# Micro.net
KiCad netlist of a schematic drawn in Altium Designer
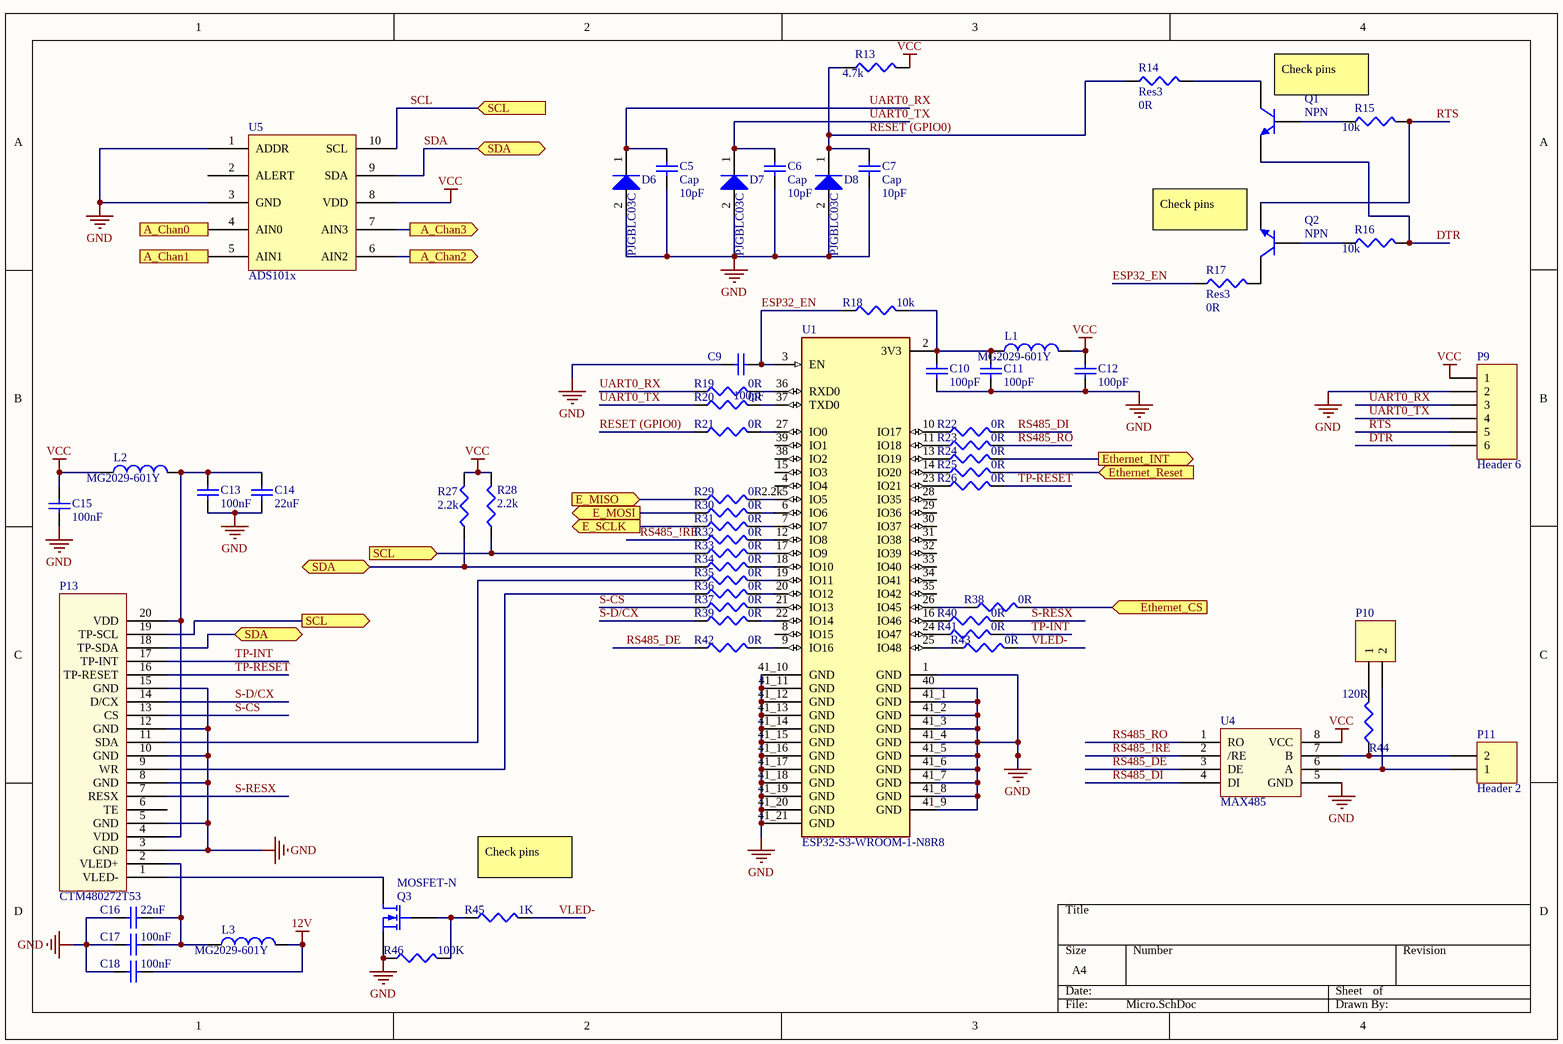
[diagram p0: Micro.SchDoc]

(export (version "E")
  (design (tool "Eeschema 10.0.6"))
  (components
    (comp (ref "C5")
      (value "Cap")
      (footprint "CAPC2012X04M")
      (description "Capacitor")
      (fields (field (name "ALTIUM_VALUE") "10pF") (field (name "PUBLISHER") "Altium Limited"))
      (libsource (lib "Miscellaneous Devices") (part "Cap"))
    )
    (comp (ref "C6")
      (value "Cap")
      (footprint "CAPC2012X04M")
      (description "Capacitor")
      (fields (field (name "ALTIUM_VALUE") "10pF") (field (name "PUBLISHER") "Altium Limited"))
      (libsource (lib "Miscellaneous Devices") (part "Cap"))
    )
    (comp (ref "C7")
      (value "Cap")
      (footprint "CAPC2012X04M")
      (description "Capacitor")
      (fields (field (name "ALTIUM_VALUE") "10pF") (field (name "PUBLISHER") "Altium Limited"))
      (libsource (lib "Miscellaneous Devices") (part "Cap"))
    )
    (comp (ref "C9")
      (value "100pF")
      (footprint "CAPC2012X04M")
      (description "Capacitor")
      (fields (field (name "Comment") "Cap") (field (name "PUBLISHER") "Altium Limited"))
      (libsource (lib "Miscellaneous Devices") (part "Cap"))
    )
    (comp (ref "C10")
      (value "100pF")
      (footprint "CAPC2012X04M")
      (description "Capacitor")
      (fields (field (name "Comment") "Cap") (field (name "PUBLISHER") "Altium Limited"))
      (libsource (lib "Miscellaneous Devices") (part "Cap"))
    )
    (comp (ref "C11")
      (value "100pF")
      (footprint "CAPC2012X04M")
      (description "Capacitor")
      (fields (field (name "Comment") "Cap") (field (name "PUBLISHER") "Altium Limited"))
      (libsource (lib "Miscellaneous Devices") (part "Cap"))
    )
    (comp (ref "C12")
      (value "100pF")
      (footprint "CAPC2012X04M")
      (description "Capacitor")
      (fields (field (name "Comment") "Cap") (field (name "PUBLISHER") "Altium Limited"))
      (libsource (lib "Miscellaneous Devices") (part "Cap"))
    )
    (comp (ref "C13")
      (value "100nF")
      (footprint "CAPC2012X04M")
      (description "Capacitor")
      (fields (field (name "Comment") "Cap") (field (name "PUBLISHER") "Altium Limited"))
      (libsource (lib "Miscellaneous Devices") (part "Cap"))
    )
    (comp (ref "C14")
      (value "22uF")
      (footprint "CAPC2012X04M")
      (description "Capacitor")
      (fields (field (name "Comment") "Cap") (field (name "PUBLISHER") "Altium Limited"))
      (libsource (lib "Miscellaneous Devices") (part "Cap"))
    )
    (comp (ref "C15")
      (value "100nF")
      (footprint "CAPC2012X04M")
      (description "Capacitor")
      (fields (field (name "Comment") "Cap") (field (name "PUBLISHER") "Altium Limited"))
      (libsource (lib "Miscellaneous Devices") (part "Cap"))
    )
    (comp (ref "C16")
      (value "22uF")
      (footprint "CAPC2012X04M")
      (description "Capacitor")
      (fields (field (name "Comment") "Cap") (field (name "PUBLISHER") "Altium Limited"))
      (libsource (lib "Miscellaneous Devices") (part "Cap"))
    )
    (comp (ref "C17")
      (value "100nF")
      (footprint "CAPC2012X04M")
      (description "Capacitor")
      (fields (field (name "Comment") "Cap") (field (name "PUBLISHER") "Altium Limited"))
      (libsource (lib "Miscellaneous Devices") (part "Cap"))
    )
    (comp (ref "C18")
      (value "100nF")
      (footprint "CAPC2012X04M")
      (description "Capacitor")
      (fields (field (name "Comment") "Cap") (field (name "PUBLISHER") "Altium Limited"))
      (libsource (lib "Miscellaneous Devices") (part "Cap"))
    )
    (comp (ref "D6")
      (value "PJGBLC03C")
      (footprint "DIOC2012X04M")
      (fields (field (name "PARTNUMBER") "SP4021-01FTG") (field (name "MANUFACTURER") "Littelfuse"))
      (libsource (lib "Diodes-TVS") (part "SP4021-01FTG"))
    )
    (comp (ref "D7")
      (value "PJGBLC03C")
      (footprint "DIOC2012X04M")
      (fields (field (name "PARTNUMBER") "SP4021-01FTG") (field (name "MANUFACTURER") "Littelfuse"))
      (libsource (lib "Diodes-TVS") (part "SP4021-01FTG"))
    )
    (comp (ref "D8")
      (value "PJGBLC03C")
      (footprint "DIOC2012X04M")
      (fields (field (name "PARTNUMBER") "SP4021-01FTG") (field (name "MANUFACTURER") "Littelfuse"))
      (libsource (lib "Diodes-TVS") (part "SP4021-01FTG"))
    )
    (comp (ref "L1")
      (value "MG2029-601Y")
      (footprint "RESC2012X04M")
      (description "Inductor")
      (fields (field (name "PUBLISHER") "Altium Limited"))
      (libsource (lib "Miscellaneous Devices") (part "Inductor"))
    )
    (comp (ref "L2")
      (value "MG2029-601Y")
      (footprint "RESC2012X04M")
      (description "Inductor")
      (fields (field (name "PUBLISHER") "Altium Limited"))
      (libsource (lib "Miscellaneous Devices") (part "Inductor"))
    )
    (comp (ref "L3")
      (value "MG2029-601Y")
      (footprint "RESC2012X04M")
      (description "Inductor")
      (fields (field (name "PUBLISHER") "Altium Limited"))
      (libsource (lib "Miscellaneous Devices") (part "Inductor"))
    )
    (comp (ref "P9")
      (value "Header 6")
      (footprint "HDR1X6")
      (description "Header, 6-Pin")
      (fields (field (name "PUBLISHER") "Altium Limited"))
      (libsource (lib "Miscellaneous Connectors") (part "Header 6"))
    )
    (comp (ref "P10")
      (value "Header 2")
      (footprint "HDR1X2")
      (description "Header, 2-Pin")
      (fields (field (name "PUBLISHER") "Altium Limited"))
      (libsource (lib "Miscellaneous Connectors") (part "Header 2"))
    )
    (comp (ref "P11")
      (value "Header 2")
      (footprint "WURTH- WR-TBL 2pin 5mmpitch")
      (description "Header, 2-Pin")
      (fields (field (name "PUBLISHER") "Altium Limited"))
      (libsource (lib "Miscellaneous Connectors") (part "Header 2"))
    )
    (comp (ref "P13")
      (value "CTM480272T53")
      (footprint "CF31201D0R0-05-NH")
      (libsource (lib "Parts") (part "CTM480272T53"))
    )
    (comp (ref "Q1")
      (value "NPN")
      (footprint "SOT95P245X110-3N")
      (description "NPN Bipolar Transistor")
      (fields (field (name "PUBLISHER") "Altium Limited"))
      (libsource (lib "Miscellaneous Devices") (part "NPN"))
    )
    (comp (ref "Q2")
      (value "NPN")
      (footprint "SOT95P245X110-3N")
      (description "NPN Bipolar Transistor")
      (fields (field (name "PUBLISHER") "Altium Limited"))
      (libsource (lib "Miscellaneous Devices") (part "NPN"))
    )
    (comp (ref "Q3")
      (value "MOSFET-N")
      (footprint "SOT95P245X110-3N")
      (description "N-Channel MOSFET")
      (fields (field (name "PUBLISHER") "Altium Limited"))
      (libsource (lib "Miscellaneous Devices") (part "MOSFET-N"))
    )
    (comp (ref "R13")
      (value "4.7k")
      (footprint "RESC2012X04M")
      (description "Resistor")
      (fields (field (name "Comment") "Res3") (field (name "PUBLISHER") "Altium Limited"))
      (libsource (lib "Miscellaneous Devices") (part "Res3"))
    )
    (comp (ref "R14")
      (value "Res3")
      (footprint "RESC2012X04M")
      (description "Resistor")
      (fields (field (name "ALTIUM_VALUE") "0R") (field (name "PUBLISHER") "Altium Limited"))
      (libsource (lib "Miscellaneous Devices") (part "Res3"))
    )
    (comp (ref "R15")
      (value "10k")
      (footprint "RESC2012X04M")
      (description "Resistor")
      (fields (field (name "Comment") "Res3") (field (name "PUBLISHER") "Altium Limited"))
      (libsource (lib "Miscellaneous Devices") (part "Res3"))
    )
    (comp (ref "R16")
      (value "10k")
      (footprint "RESC2012X04M")
      (description "Resistor")
      (fields (field (name "Comment") "Res3") (field (name "PUBLISHER") "Altium Limited"))
      (libsource (lib "Miscellaneous Devices") (part "Res3"))
    )
    (comp (ref "R17")
      (value "Res3")
      (footprint "RESC2012X04M")
      (description "Resistor")
      (fields (field (name "ALTIUM_VALUE") "0R") (field (name "PUBLISHER") "Altium Limited"))
      (libsource (lib "Miscellaneous Devices") (part "Res3"))
    )
    (comp (ref "R18")
      (value "10k")
      (footprint "RESC2012X04M")
      (description "Resistor")
      (fields (field (name "Comment") "Res3") (field (name "PUBLISHER") "Altium Limited"))
      (libsource (lib "Miscellaneous Devices") (part "Res3"))
    )
    (comp (ref "R19")
      (value "0R")
      (footprint "RESC2012X04M")
      (description "Resistor")
      (fields (field (name "Comment") "Res3") (field (name "PUBLISHER") "Altium Limited"))
      (libsource (lib "Miscellaneous Devices") (part "Res3"))
    )
    (comp (ref "R20")
      (value "0R")
      (footprint "RESC2012X04M")
      (description "Resistor")
      (fields (field (name "Comment") "Res3") (field (name "PUBLISHER") "Altium Limited"))
      (libsource (lib "Miscellaneous Devices") (part "Res3"))
    )
    (comp (ref "R21")
      (value "0R")
      (footprint "RESC2012X04M")
      (description "Resistor")
      (fields (field (name "Comment") "Res3") (field (name "PUBLISHER") "Altium Limited"))
      (libsource (lib "Miscellaneous Devices") (part "Res3"))
    )
    (comp (ref "R22")
      (value "0R")
      (footprint "RESC2012X04M")
      (description "Resistor")
      (fields (field (name "Comment") "Res3") (field (name "PUBLISHER") "Altium Limited"))
      (libsource (lib "Miscellaneous Devices") (part "Res3"))
    )
    (comp (ref "R23")
      (value "0R")
      (footprint "RESC2012X04M")
      (description "Resistor")
      (fields (field (name "Comment") "Res3") (field (name "PUBLISHER") "Altium Limited"))
      (libsource (lib "Miscellaneous Devices") (part "Res3"))
    )
    (comp (ref "R24")
      (value "0R")
      (footprint "RESC2012X04M")
      (description "Resistor")
      (fields (field (name "Comment") "Res3") (field (name "PUBLISHER") "Altium Limited"))
      (libsource (lib "Miscellaneous Devices") (part "Res3"))
    )
    (comp (ref "R25")
      (value "0R")
      (footprint "RESC2012X04M")
      (description "Resistor")
      (fields (field (name "Comment") "Res3") (field (name "PUBLISHER") "Altium Limited"))
      (libsource (lib "Miscellaneous Devices") (part "Res3"))
    )
    (comp (ref "R26")
      (value "0R")
      (footprint "RESC2012X04M")
      (description "Resistor")
      (fields (field (name "Comment") "Res3") (field (name "PUBLISHER") "Altium Limited"))
      (libsource (lib "Miscellaneous Devices") (part "Res3"))
    )
    (comp (ref "R27")
      (value "2.2k")
      (footprint "RESC2012X04M")
      (description "Resistor")
      (fields (field (name "Comment") "Res3") (field (name "PUBLISHER") "Altium Limited"))
      (libsource (lib "Miscellaneous Devices") (part "Res3"))
    )
    (comp (ref "R28")
      (value "2.2k")
      (footprint "RESC2012X04M")
      (description "Resistor")
      (fields (field (name "Comment") "Res3") (field (name "PUBLISHER") "Altium Limited"))
      (libsource (lib "Miscellaneous Devices") (part "Res3"))
    )
    (comp (ref "R29")
      (value "0R")
      (footprint "RESC2012X04M")
      (description "Resistor")
      (fields (field (name "Comment") "Res3") (field (name "PUBLISHER") "Altium Limited"))
      (libsource (lib "Miscellaneous Devices") (part "Res3"))
    )
    (comp (ref "R30")
      (value "0R")
      (footprint "RESC2012X04M")
      (description "Resistor")
      (fields (field (name "Comment") "Res3") (field (name "PUBLISHER") "Altium Limited"))
      (libsource (lib "Miscellaneous Devices") (part "Res3"))
    )
    (comp (ref "R31")
      (value "0R")
      (footprint "RESC2012X04M")
      (description "Resistor")
      (fields (field (name "Comment") "Res3") (field (name "PUBLISHER") "Altium Limited"))
      (libsource (lib "Miscellaneous Devices") (part "Res3"))
    )
    (comp (ref "R32")
      (value "0R")
      (footprint "RESC2012X04M")
      (description "Resistor")
      (fields (field (name "Comment") "Res3") (field (name "PUBLISHER") "Altium Limited"))
      (libsource (lib "Miscellaneous Devices") (part "Res3"))
    )
    (comp (ref "R33")
      (value "0R")
      (footprint "RESC2012X04M")
      (description "Resistor")
      (fields (field (name "Comment") "Res3") (field (name "PUBLISHER") "Altium Limited"))
      (libsource (lib "Miscellaneous Devices") (part "Res3"))
    )
    (comp (ref "R34")
      (value "0R")
      (footprint "RESC2012X04M")
      (description "Resistor")
      (fields (field (name "Comment") "Res3") (field (name "PUBLISHER") "Altium Limited"))
      (libsource (lib "Miscellaneous Devices") (part "Res3"))
    )
    (comp (ref "R35")
      (value "0R")
      (footprint "RESC2012X04M")
      (description "Resistor")
      (fields (field (name "Comment") "Res3") (field (name "PUBLISHER") "Altium Limited"))
      (libsource (lib "Miscellaneous Devices") (part "Res3"))
    )
    (comp (ref "R36")
      (value "0R")
      (footprint "RESC2012X04M")
      (description "Resistor")
      (fields (field (name "Comment") "Res3") (field (name "PUBLISHER") "Altium Limited"))
      (libsource (lib "Miscellaneous Devices") (part "Res3"))
    )
    (comp (ref "R37")
      (value "0R")
      (footprint "RESC2012X04M")
      (description "Resistor")
      (fields (field (name "Comment") "Res3") (field (name "PUBLISHER") "Altium Limited"))
      (libsource (lib "Miscellaneous Devices") (part "Res3"))
    )
    (comp (ref "R38")
      (value "0R")
      (footprint "RESC2012X04M")
      (description "Resistor")
      (fields (field (name "Comment") "Res3") (field (name "PUBLISHER") "Altium Limited"))
      (libsource (lib "Miscellaneous Devices") (part "Res3"))
    )
    (comp (ref "R39")
      (value "0R")
      (footprint "RESC2012X04M")
      (description "Resistor")
      (fields (field (name "Comment") "Res3") (field (name "PUBLISHER") "Altium Limited"))
      (libsource (lib "Miscellaneous Devices") (part "Res3"))
    )
    (comp (ref "R40")
      (value "0R")
      (footprint "RESC2012X04M")
      (description "Resistor")
      (fields (field (name "Comment") "Res3") (field (name "PUBLISHER") "Altium Limited"))
      (libsource (lib "Miscellaneous Devices") (part "Res3"))
    )
    (comp (ref "R41")
      (value "0R")
      (footprint "RESC2012X04M")
      (description "Resistor")
      (fields (field (name "Comment") "Res3") (field (name "PUBLISHER") "Altium Limited"))
      (libsource (lib "Miscellaneous Devices") (part "Res3"))
    )
    (comp (ref "R42")
      (value "0R")
      (footprint "RESC2012X04M")
      (description "Resistor")
      (fields (field (name "Comment") "Res3") (field (name "PUBLISHER") "Altium Limited"))
      (libsource (lib "Miscellaneous Devices") (part "Res3"))
    )
    (comp (ref "R43")
      (value "0R")
      (footprint "RESC2012X04M")
      (description "Resistor")
      (fields (field (name "Comment") "Res3") (field (name "PUBLISHER") "Altium Limited"))
      (libsource (lib "Miscellaneous Devices") (part "Res3"))
    )
    (comp (ref "R44")
      (value "120R")
      (footprint "RESC2012X04M")
      (description "Resistor")
      (fields (field (name "Comment") "Res3") (field (name "PUBLISHER") "Altium Limited"))
      (libsource (lib "Miscellaneous Devices") (part "Res3"))
    )
    (comp (ref "R45")
      (value "1K")
      (footprint "RESC2012X04M")
      (description "Resistor")
      (fields (field (name "Comment") "Res3") (field (name "PUBLISHER") "Altium Limited"))
      (libsource (lib "Miscellaneous Devices") (part "Res3"))
    )
    (comp (ref "R46")
      (value "100K")
      (footprint "RESC2012X04M")
      (description "Resistor")
      (fields (field (name "Comment") "Res3") (field (name "PUBLISHER") "Altium Limited"))
      (libsource (lib "Miscellaneous Devices") (part "Res3"))
    )
    (comp (ref "U1")
      (value "ESP32-S3-WROOM-1-N8R8")
      (footprint "XCVR_ESP32S3WROOM1N8R8")
      (description "Bluetooth, WiFi 802.11b/g/n, Bluetooth v5.0 Transceiver Module 2.4GHz PCB Trace Surface Mount")
      (fields (field (name "MF") "Espressif Systems"))
      (libsource (lib "ESP32-S3-WROOM-1-N8R8") (part "ESP32-S3-WROOM-1-N8R8"))
    )
    (comp (ref "U4")
      (value "MAX485")
      (footprint "SOIC127P600X155-8N")
      (libsource (lib "Parts") (part "MAX485"))
    )
    (comp (ref "U5") (value "ADS101x") (footprint "VSSOP_10") (libsource (lib "Parts") (part "ADS101x")))
  )
  (nets
    (net (code "1") (name "/A_Chan0") (class "Default")
      (node (ref "U5") (pin "4") (pinfunction "AIN0_4") (pintype "passive"))
    )
    (net (code "2") (name "/A_Chan1") (class "Default")
      (node (ref "U5") (pin "5") (pinfunction "AIN1_5") (pintype "passive"))
    )
    (net (code "3") (name "/A_Chan2") (class "Default")
      (node (ref "U5") (pin "6") (pinfunction "AIN2_6") (pintype "passive"))
    )
    (net (code "4") (name "/A_Chan3") (class "Default")
      (node (ref "U5") (pin "7") (pinfunction "AIN3_7") (pintype "passive"))
    )
    (net (code "5") (name "/DTR") (class "Default")
      (node (ref "P9") (pin "6") (pinfunction "6_6") (pintype "passive"))
      (node (ref "Q1") (pin "3") (pinfunction "E_3") (pintype "passive"))
      (node (ref "R16") (pin "2") (pinfunction "2_2") (pintype "passive"))
    )
    (net (code "6") (name "/ESP32_EN") (class "Default")
      (node (ref "C9") (pin "1") (pinfunction "1_1") (pintype "passive"))
      (node (ref "R17") (pin "1") (pinfunction "1_1") (pintype "passive"))
      (node (ref "R18") (pin "1") (pinfunction "1_1") (pintype "passive"))
      (node (ref "U1") (pin "3") (pinfunction "EN_3") (pintype "input"))
    )
    (net (code "7") (name "/E_MISO") (class "Default")
      (node (ref "R29") (pin "1") (pinfunction "1_1") (pintype "passive"))
    )
    (net (code "8") (name "/E_MOSI") (class "Default")
      (node (ref "R30") (pin "1") (pinfunction "1_1") (pintype "passive"))
    )
    (net (code "9") (name "/E_SCLK") (class "Default")
      (node (ref "R31") (pin "1") (pinfunction "1_1") (pintype "passive"))
    )
    (net (code "10") (name "/Ethernet_CS") (class "Default")
      (node (ref "R38") (pin "2") (pinfunction "2_2") (pintype "passive"))
    )
    (net (code "11") (name "/Ethernet_INT") (class "Default")
      (node (ref "R24") (pin "2") (pinfunction "2_2") (pintype "passive"))
    )
    (net (code "12") (name "/Ethernet_Reset") (class "Default")
      (node (ref "R25") (pin "2") (pinfunction "2_2") (pintype "passive"))
    )
    (net (code "13") (name "/RESET (GPIO0)") (class "Default")
      (node (ref "C7") (pin "2") (pinfunction "2_2") (pintype "passive"))
      (node (ref "D8") (pin "1") (pinfunction "K_1") (pintype "passive"))
      (node (ref "R13") (pin "1") (pinfunction "1_1") (pintype "passive"))
      (node (ref "R14") (pin "1") (pinfunction "1_1") (pintype "passive"))
      (node (ref "R21") (pin "1") (pinfunction "1_1") (pintype "passive"))
    )
    (net (code "14") (name "/RS485_!RE") (class "Default")
      (node (ref "R32") (pin "1") (pinfunction "1_1") (pintype "passive"))
      (node (ref "U4") (pin "2") (pinfunction "/RE_2") (pintype "passive"))
    )
    (net (code "15") (name "/RS485_DE") (class "Default")
      (node (ref "R42") (pin "1") (pinfunction "1_1") (pintype "passive"))
      (node (ref "U4") (pin "3") (pinfunction "DE_3") (pintype "passive"))
    )
    (net (code "16") (name "/RS485_DI") (class "Default")
      (node (ref "R22") (pin "2") (pinfunction "2_2") (pintype "passive"))
      (node (ref "U4") (pin "4") (pinfunction "DI_4") (pintype "passive"))
    )
    (net (code "17") (name "/RS485_RO") (class "Default")
      (node (ref "R23") (pin "2") (pinfunction "2_2") (pintype "passive"))
      (node (ref "U4") (pin "1") (pinfunction "RO_1") (pintype "passive"))
    )
    (net (code "18") (name "/RTS") (class "Default")
      (node (ref "P9") (pin "5") (pinfunction "5_5") (pintype "passive"))
      (node (ref "Q2") (pin "3") (pinfunction "E_3") (pintype "passive"))
      (node (ref "R15") (pin "2") (pinfunction "2_2") (pintype "passive"))
    )
    (net (code "19") (name "/S-CS") (class "Default")
      (node (ref "P13") (pin "13") (pinfunction "CS_13") (pintype "passive"))
      (node (ref "R37") (pin "1") (pinfunction "1_1") (pintype "passive"))
    )
    (net (code "20") (name "/S-D{slash}CX") (class "Default")
      (node (ref "P13") (pin "14") (pinfunction "D/CX_14") (pintype "passive"))
      (node (ref "R39") (pin "1") (pinfunction "1_1") (pintype "passive"))
    )
    (net (code "21") (name "/S-RESX") (class "Default")
      (node (ref "P13") (pin "7") (pinfunction "RESX_7") (pintype "passive"))
      (node (ref "R40") (pin "2") (pinfunction "2_2") (pintype "passive"))
    )
    (net (code "22") (name "/SCL") (class "Default")
      (node (ref "P13") (pin "19") (pinfunction "TP-SCL_19") (pintype "passive"))
      (node (ref "R28") (pin "1") (pinfunction "1_1") (pintype "passive"))
      (node (ref "R33") (pin "1") (pinfunction "1_1") (pintype "passive"))
      (node (ref "U5") (pin "10") (pinfunction "SCL_10") (pintype "passive"))
    )
    (net (code "23") (name "/SDA") (class "Default")
      (node (ref "P13") (pin "18") (pinfunction "TP-SDA_18") (pintype "passive"))
      (node (ref "R27") (pin "1") (pinfunction "1_1") (pintype "passive"))
      (node (ref "R34") (pin "1") (pinfunction "1_1") (pintype "passive"))
      (node (ref "U5") (pin "9") (pinfunction "SDA_9") (pintype "passive"))
    )
    (net (code "24") (name "/TP-INT") (class "Default")
      (node (ref "P13") (pin "17") (pinfunction "TP-INT_17") (pintype "passive"))
      (node (ref "R41") (pin "2") (pinfunction "2_2") (pintype "passive"))
    )
    (net (code "25") (name "/TP-RESET") (class "Default")
      (node (ref "P13") (pin "16") (pinfunction "TP-RESET_16") (pintype "passive"))
      (node (ref "R26") (pin "2") (pinfunction "2_2") (pintype "passive"))
    )
    (net (code "26") (name "/UART0_RX") (class "Default")
      (node (ref "C5") (pin "2") (pinfunction "2_2") (pintype "passive"))
      (node (ref "D6") (pin "1") (pinfunction "K_1") (pintype "passive"))
      (node (ref "P9") (pin "3") (pinfunction "3_3") (pintype "passive"))
      (node (ref "R19") (pin "1") (pinfunction "1_1") (pintype "passive"))
    )
    (net (code "27") (name "/UART0_TX") (class "Default")
      (node (ref "C6") (pin "2") (pinfunction "2_2") (pintype "passive"))
      (node (ref "D7") (pin "1") (pinfunction "K_1") (pintype "passive"))
      (node (ref "P9") (pin "4") (pinfunction "4_4") (pintype "passive"))
      (node (ref "R20") (pin "1") (pinfunction "1_1") (pintype "passive"))
    )
    (net (code "28") (name "/VLED-") (class "Default")
      (node (ref "R43") (pin "2") (pinfunction "2_2") (pintype "passive"))
      (node (ref "R45") (pin "2") (pinfunction "2_2") (pintype "passive"))
    )
    (net (code "29") (name "12V") (class "Default")
      (node (ref "C18") (pin "1") (pinfunction "1_1") (pintype "passive"))
      (node (ref "L3") (pin "2") (pinfunction "2_2") (pintype "passive"))
    )
    (net (code "30") (name "GND") (class "Default")
      (node (ref "C10") (pin "2") (pinfunction "2_2") (pintype "passive"))
      (node (ref "C11") (pin "2") (pinfunction "2_2") (pintype "passive"))
      (node (ref "C12") (pin "2") (pinfunction "2_2") (pintype "passive"))
      (node (ref "C13") (pin "2") (pinfunction "2_2") (pintype "passive"))
      (node (ref "C14") (pin "2") (pinfunction "2_2") (pintype "passive"))
      (node (ref "C15") (pin "2") (pinfunction "2_2") (pintype "passive"))
      (node (ref "C16") (pin "2") (pinfunction "2_2") (pintype "passive"))
      (node (ref "C17") (pin "2") (pinfunction "2_2") (pintype "passive"))
      (node (ref "C18") (pin "2") (pinfunction "2_2") (pintype "passive"))
      (node (ref "C5") (pin "1") (pinfunction "1_1") (pintype "passive"))
      (node (ref "C6") (pin "1") (pinfunction "1_1") (pintype "passive"))
      (node (ref "C7") (pin "1") (pinfunction "1_1") (pintype "passive"))
      (node (ref "C9") (pin "2") (pinfunction "2_2") (pintype "passive"))
      (node (ref "D6") (pin "2") (pinfunction "A_2") (pintype "passive"))
      (node (ref "D7") (pin "2") (pinfunction "A_2") (pintype "passive"))
      (node (ref "D8") (pin "2") (pinfunction "A_2") (pintype "passive"))
      (node (ref "P13") (pin "10") (pinfunction "GND_10") (pintype "passive"))
      (node (ref "P13") (pin "12") (pinfunction "GND_12") (pintype "passive"))
      (node (ref "P13") (pin "15") (pinfunction "GND_15") (pintype "passive"))
      (node (ref "P13") (pin "3") (pinfunction "GND_3") (pintype "passive"))
      (node (ref "P13") (pin "5") (pinfunction "GND_5") (pintype "passive"))
      (node (ref "P13") (pin "8") (pinfunction "GND_8") (pintype "passive"))
      (node (ref "P9") (pin "2") (pinfunction "2_2") (pintype "passive"))
      (node (ref "Q3") (pin "3") (pinfunction "S_3") (pintype "passive"))
      (node (ref "R46") (pin "1") (pinfunction "1_1") (pintype "passive"))
      (node (ref "U1") (pin "1") (pinfunction "GND_1") (pintype "power_in"))
      (node (ref "U1") (pin "40") (pinfunction "GND_40") (pintype "power_in"))
      (node (ref "U1") (pin "41_1") (pinfunction "GND_41_1") (pintype "power_in"))
      (node (ref "U1") (pin "41_10") (pinfunction "GND_41_10") (pintype "passive"))
      (node (ref "U1") (pin "41_11") (pinfunction "GND_41_11") (pintype "passive"))
      (node (ref "U1") (pin "41_12") (pinfunction "GND_41_12") (pintype "passive"))
      (node (ref "U1") (pin "41_13") (pinfunction "GND_41_13") (pintype "passive"))
      (node (ref "U1") (pin "41_14") (pinfunction "GND_41_14") (pintype "passive"))
      (node (ref "U1") (pin "41_15") (pinfunction "GND_41_15") (pintype "passive"))
      (node (ref "U1") (pin "41_16") (pinfunction "GND_41_16") (pintype "passive"))
      (node (ref "U1") (pin "41_17") (pinfunction "GND_41_17") (pintype "passive"))
      (node (ref "U1") (pin "41_18") (pinfunction "GND_41_18") (pintype "passive"))
      (node (ref "U1") (pin "41_19") (pinfunction "GND_41_19") (pintype "passive"))
      (node (ref "U1") (pin "41_2") (pinfunction "GND_41_2") (pintype "power_in"))
      (node (ref "U1") (pin "41_20") (pinfunction "GND_41_20") (pintype "passive"))
      (node (ref "U1") (pin "41_21") (pinfunction "GND_41_21") (pintype "passive"))
      (node (ref "U1") (pin "41_3") (pinfunction "GND_41_3") (pintype "power_in"))
      (node (ref "U1") (pin "41_4") (pinfunction "GND_41_4") (pintype "power_in"))
      (node (ref "U1") (pin "41_5") (pinfunction "GND_41_5") (pintype "power_in"))
      (node (ref "U1") (pin "41_6") (pinfunction "GND_41_6") (pintype "power_in"))
      (node (ref "U1") (pin "41_7") (pinfunction "GND_41_7") (pintype "power_in"))
      (node (ref "U1") (pin "41_8") (pinfunction "GND_41_8") (pintype "power_in"))
      (node (ref "U1") (pin "41_9") (pinfunction "GND_41_9") (pintype "power_in"))
      (node (ref "U4") (pin "5") (pinfunction "GND_5") (pintype "passive"))
      (node (ref "U5") (pin "1") (pinfunction "ADDR_1") (pintype "passive"))
      (node (ref "U5") (pin "3") (pinfunction "GND_3") (pintype "passive"))
    )
    (net (code "31") (name "Net-(C13-Pad1)") (class "Default")
      (node (ref "C13") (pin "1") (pinfunction "1_1") (pintype "passive"))
      (node (ref "C14") (pin "1") (pinfunction "1_1") (pintype "passive"))
      (node (ref "L2") (pin "2") (pinfunction "2_2") (pintype "passive"))
      (node (ref "P13") (pin "20") (pinfunction "VDD_20") (pintype "passive"))
      (node (ref "P13") (pin "4") (pinfunction "VDD_4") (pintype "passive"))
    )
    (net (code "32") (name "Net-(P10-Pad1)") (class "Default")
      (node (ref "P10") (pin "1") (pinfunction "1_1") (pintype "passive"))
      (node (ref "R44") (pin "2") (pinfunction "2_2") (pintype "passive"))
    )
    (net (code "33") (name "Net-(P13-SDA)") (class "Default")
      (node (ref "P13") (pin "11") (pinfunction "SDA_11") (pintype "passive"))
      (node (ref "R35") (pin "1") (pinfunction "1_1") (pintype "passive"))
    )
    (net (code "34") (name "Net-(P13-VLED+)") (class "Default")
      (node (ref "C16") (pin "1") (pinfunction "1_1") (pintype "passive"))
      (node (ref "C17") (pin "1") (pinfunction "1_1") (pintype "passive"))
      (node (ref "L3") (pin "1") (pinfunction "1_1") (pintype "passive"))
      (node (ref "P13") (pin "2") (pinfunction "VLED+_2") (pintype "passive"))
    )
    (net (code "35") (name "Net-(P13-VLED-)") (class "Default")
      (node (ref "P13") (pin "1") (pinfunction "VLED-_1") (pintype "passive"))
      (node (ref "Q3") (pin "1") (pinfunction "D_1") (pintype "passive"))
    )
    (net (code "36") (name "Net-(P13-WR)") (class "Default")
      (node (ref "P13") (pin "9") (pinfunction "WR_9") (pintype "passive"))
      (node (ref "R36") (pin "1") (pinfunction "1_1") (pintype "passive"))
    )
    (net (code "37") (name "Net-(Q1-B)") (class "Default")
      (node (ref "Q1") (pin "2") (pinfunction "B_2") (pintype "passive"))
      (node (ref "R15") (pin "1") (pinfunction "1_1") (pintype "passive"))
    )
    (net (code "38") (name "Net-(Q1-C)") (class "Default")
      (node (ref "Q1") (pin "1") (pinfunction "C_1") (pintype "passive"))
      (node (ref "R14") (pin "2") (pinfunction "2_2") (pintype "passive"))
    )
    (net (code "39") (name "Net-(Q2-B)") (class "Default")
      (node (ref "Q2") (pin "2") (pinfunction "B_2") (pintype "passive"))
      (node (ref "R16") (pin "1") (pinfunction "1_1") (pintype "passive"))
    )
    (net (code "40") (name "Net-(Q2-C)") (class "Default")
      (node (ref "Q2") (pin "1") (pinfunction "C_1") (pintype "passive"))
      (node (ref "R17") (pin "2") (pinfunction "2_2") (pintype "passive"))
    )
    (net (code "41") (name "Net-(Q3-G)") (class "Default")
      (node (ref "Q3") (pin "2") (pinfunction "G_2") (pintype "passive"))
      (node (ref "R45") (pin "1") (pinfunction "1_1") (pintype "passive"))
      (node (ref "R46") (pin "2") (pinfunction "2_2") (pintype "passive"))
    )
    (net (code "42") (name "Net-(U1-3V3)") (class "Default")
      (node (ref "C10") (pin "1") (pinfunction "1_1") (pintype "passive"))
      (node (ref "C11") (pin "1") (pinfunction "1_1") (pintype "passive"))
      (node (ref "L1") (pin "1") (pinfunction "1_1") (pintype "passive"))
      (node (ref "R18") (pin "2") (pinfunction "2_2") (pintype "passive"))
      (node (ref "U1") (pin "2") (pinfunction "3V3_2") (pintype "power_in"))
    )
    (net (code "43") (name "Net-(U1-IO0)") (class "Default")
      (node (ref "R21") (pin "2") (pinfunction "2_2") (pintype "passive"))
      (node (ref "U1") (pin "27") (pinfunction "IO0_27") (pintype "bidirectional"))
    )
    (net (code "44") (name "Net-(U1-IO5)") (class "Default")
      (node (ref "R29") (pin "2") (pinfunction "2_2") (pintype "passive"))
      (node (ref "U1") (pin "5") (pinfunction "IO5_5") (pintype "bidirectional"))
    )
    (net (code "45") (name "Net-(U1-IO6)") (class "Default")
      (node (ref "R30") (pin "2") (pinfunction "2_2") (pintype "passive"))
      (node (ref "U1") (pin "6") (pinfunction "IO6_6") (pintype "bidirectional"))
    )
    (net (code "46") (name "Net-(U1-IO7)") (class "Default")
      (node (ref "R31") (pin "2") (pinfunction "2_2") (pintype "passive"))
      (node (ref "U1") (pin "7") (pinfunction "IO7_7") (pintype "bidirectional"))
    )
    (net (code "47") (name "Net-(U1-IO8)") (class "Default")
      (node (ref "R32") (pin "2") (pinfunction "2_2") (pintype "passive"))
      (node (ref "U1") (pin "12") (pinfunction "IO8_12") (pintype "bidirectional"))
    )
    (net (code "48") (name "Net-(U1-IO9)") (class "Default")
      (node (ref "R33") (pin "2") (pinfunction "2_2") (pintype "passive"))
      (node (ref "U1") (pin "17") (pinfunction "IO9_17") (pintype "bidirectional"))
    )
    (net (code "49") (name "Net-(U1-IO10)") (class "Default")
      (node (ref "R34") (pin "2") (pinfunction "2_2") (pintype "passive"))
      (node (ref "U1") (pin "18") (pinfunction "IO10_18") (pintype "bidirectional"))
    )
    (net (code "50") (name "Net-(U1-IO11)") (class "Default")
      (node (ref "R35") (pin "2") (pinfunction "2_2") (pintype "passive"))
      (node (ref "U1") (pin "19") (pinfunction "IO11_19") (pintype "bidirectional"))
    )
    (net (code "51") (name "Net-(U1-IO12)") (class "Default")
      (node (ref "R36") (pin "2") (pinfunction "2_2") (pintype "passive"))
      (node (ref "U1") (pin "20") (pinfunction "IO12_20") (pintype "bidirectional"))
    )
    (net (code "52") (name "Net-(U1-IO13)") (class "Default")
      (node (ref "R37") (pin "2") (pinfunction "2_2") (pintype "passive"))
      (node (ref "U1") (pin "21") (pinfunction "IO13_21") (pintype "bidirectional"))
    )
    (net (code "53") (name "Net-(U1-IO14)") (class "Default")
      (node (ref "R39") (pin "2") (pinfunction "2_2") (pintype "passive"))
      (node (ref "U1") (pin "22") (pinfunction "IO14_22") (pintype "bidirectional"))
    )
    (net (code "54") (name "Net-(U1-IO16)") (class "Default")
      (node (ref "R42") (pin "2") (pinfunction "2_2") (pintype "passive"))
      (node (ref "U1") (pin "9") (pinfunction "IO16_9") (pintype "bidirectional"))
    )
    (net (code "55") (name "Net-(U1-IO17)") (class "Default")
      (node (ref "R22") (pin "1") (pinfunction "1_1") (pintype "passive"))
      (node (ref "U1") (pin "10") (pinfunction "IO17_10") (pintype "bidirectional"))
    )
    (net (code "56") (name "Net-(U1-IO18)") (class "Default")
      (node (ref "R23") (pin "1") (pinfunction "1_1") (pintype "passive"))
      (node (ref "U1") (pin "11") (pinfunction "IO18_11") (pintype "bidirectional"))
    )
    (net (code "57") (name "Net-(U1-IO19)") (class "Default")
      (node (ref "R24") (pin "1") (pinfunction "1_1") (pintype "passive"))
      (node (ref "U1") (pin "13") (pinfunction "IO19_13") (pintype "bidirectional"))
    )
    (net (code "58") (name "Net-(U1-IO20)") (class "Default")
      (node (ref "R25") (pin "1") (pinfunction "1_1") (pintype "passive"))
      (node (ref "U1") (pin "14") (pinfunction "IO20_14") (pintype "bidirectional"))
    )
    (net (code "59") (name "Net-(U1-IO21)") (class "Default")
      (node (ref "R26") (pin "1") (pinfunction "1_1") (pintype "passive"))
      (node (ref "U1") (pin "23") (pinfunction "IO21_23") (pintype "bidirectional"))
    )
    (net (code "60") (name "Net-(U1-IO45)") (class "Default")
      (node (ref "R38") (pin "1") (pinfunction "1_1") (pintype "passive"))
      (node (ref "U1") (pin "26") (pinfunction "IO45_26") (pintype "bidirectional"))
    )
    (net (code "61") (name "Net-(U1-IO46)") (class "Default")
      (node (ref "R40") (pin "1") (pinfunction "1_1") (pintype "passive"))
      (node (ref "U1") (pin "16") (pinfunction "IO46_16") (pintype "bidirectional"))
    )
    (net (code "62") (name "Net-(U1-IO47)") (class "Default")
      (node (ref "R41") (pin "1") (pinfunction "1_1") (pintype "passive"))
      (node (ref "U1") (pin "24") (pinfunction "IO47_24") (pintype "bidirectional"))
    )
    (net (code "63") (name "Net-(U1-IO48)") (class "Default")
      (node (ref "R43") (pin "1") (pinfunction "1_1") (pintype "passive"))
      (node (ref "U1") (pin "25") (pinfunction "IO48_25") (pintype "bidirectional"))
    )
    (net (code "64") (name "Net-(U1-RXD0)") (class "Default")
      (node (ref "R19") (pin "2") (pinfunction "2_2") (pintype "passive"))
      (node (ref "U1") (pin "36") (pinfunction "RXD0_36") (pintype "bidirectional"))
    )
    (net (code "65") (name "Net-(U1-TXD0)") (class "Default")
      (node (ref "R20") (pin "2") (pinfunction "2_2") (pintype "passive"))
      (node (ref "U1") (pin "37") (pinfunction "TXD0_37") (pintype "bidirectional"))
    )
    (net (code "66") (name "Net-(U4-A)") (class "Default")
      (node (ref "P10") (pin "2") (pinfunction "2_2") (pintype "passive"))
      (node (ref "P11") (pin "1") (pinfunction "1_1") (pintype "passive"))
      (node (ref "U4") (pin "6") (pinfunction "A_6") (pintype "passive"))
    )
    (net (code "67") (name "Net-(U4-B)") (class "Default")
      (node (ref "P11") (pin "2") (pinfunction "2_2") (pintype "passive"))
      (node (ref "R44") (pin "1") (pinfunction "1_1") (pintype "passive"))
      (node (ref "U4") (pin "7") (pinfunction "B_7") (pintype "passive"))
    )
    (net (code "68") (name "VCC") (class "Default")
      (node (ref "C12") (pin "1") (pinfunction "1_1") (pintype "passive"))
      (node (ref "C15") (pin "1") (pinfunction "1_1") (pintype "passive"))
      (node (ref "L1") (pin "2") (pinfunction "2_2") (pintype "passive"))
      (node (ref "L2") (pin "1") (pinfunction "1_1") (pintype "passive"))
      (node (ref "P9") (pin "1") (pinfunction "1_1") (pintype "passive"))
      (node (ref "R13") (pin "2") (pinfunction "2_2") (pintype "passive"))
      (node (ref "R27") (pin "2") (pinfunction "2_2") (pintype "passive"))
      (node (ref "R28") (pin "2") (pinfunction "2_2") (pintype "passive"))
      (node (ref "U4") (pin "8") (pinfunction "VCC_8") (pintype "passive"))
      (node (ref "U5") (pin "8") (pinfunction "VDD_8") (pintype "passive"))
    )
    (net (code "69") (name "unconnected-(P13-TE-Pad6)") (class "Default")
      (node (ref "P13") (pin "6") (pinfunction "TE_6") (pintype "passive"))
    )
    (net (code "70") (name "unconnected-(U1-IO1-Pad39)") (class "Default")
      (node (ref "U1") (pin "39") (pinfunction "IO1_39") (pintype "bidirectional"))
    )
    (net (code "71") (name "unconnected-(U1-IO2-Pad38)") (class "Default")
      (node (ref "U1") (pin "38") (pinfunction "IO2_38") (pintype "bidirectional"))
    )
    (net (code "72") (name "unconnected-(U1-IO3-Pad15)") (class "Default")
      (node (ref "U1") (pin "15") (pinfunction "IO3_15") (pintype "bidirectional"))
    )
    (net (code "73") (name "unconnected-(U1-IO4-Pad4)") (class "Default")
      (node (ref "U1") (pin "4") (pinfunction "IO4_4") (pintype "bidirectional"))
    )
    (net (code "74") (name "unconnected-(U1-IO15-Pad8)") (class "Default")
      (node (ref "U1") (pin "8") (pinfunction "IO15_8") (pintype "bidirectional"))
    )
    (net (code "75") (name "unconnected-(U1-IO35-Pad28)") (class "Default")
      (node (ref "U1") (pin "28") (pinfunction "IO35_28") (pintype "bidirectional"))
    )
    (net (code "76") (name "unconnected-(U1-IO36-Pad29)") (class "Default")
      (node (ref "U1") (pin "29") (pinfunction "IO36_29") (pintype "bidirectional"))
    )
    (net (code "77") (name "unconnected-(U1-IO37-Pad30)") (class "Default")
      (node (ref "U1") (pin "30") (pinfunction "IO37_30") (pintype "bidirectional"))
    )
    (net (code "78") (name "unconnected-(U1-IO38-Pad31)") (class "Default")
      (node (ref "U1") (pin "31") (pinfunction "IO38_31") (pintype "bidirectional"))
    )
    (net (code "79") (name "unconnected-(U1-IO39-Pad32)") (class "Default")
      (node (ref "U1") (pin "32") (pinfunction "IO39_32") (pintype "bidirectional"))
    )
    (net (code "80") (name "unconnected-(U1-IO40-Pad33)") (class "Default")
      (node (ref "U1") (pin "33") (pinfunction "IO40_33") (pintype "bidirectional"))
    )
    (net (code "81") (name "unconnected-(U1-IO41-Pad34)") (class "Default")
      (node (ref "U1") (pin "34") (pinfunction "IO41_34") (pintype "bidirectional"))
    )
    (net (code "82") (name "unconnected-(U1-IO42-Pad35)") (class "Default")
      (node (ref "U1") (pin "35") (pinfunction "IO42_35") (pintype "bidirectional"))
    )
    (net (code "83") (name "unconnected-(U5-ALERT-Pad2)") (class "Default")
      (node (ref "U5") (pin "2") (pinfunction "ALERT_2") (pintype "passive"))
    )
  )
)
